# powerpartial.net
KiCad netlist of a schematic drawn in EAGLE
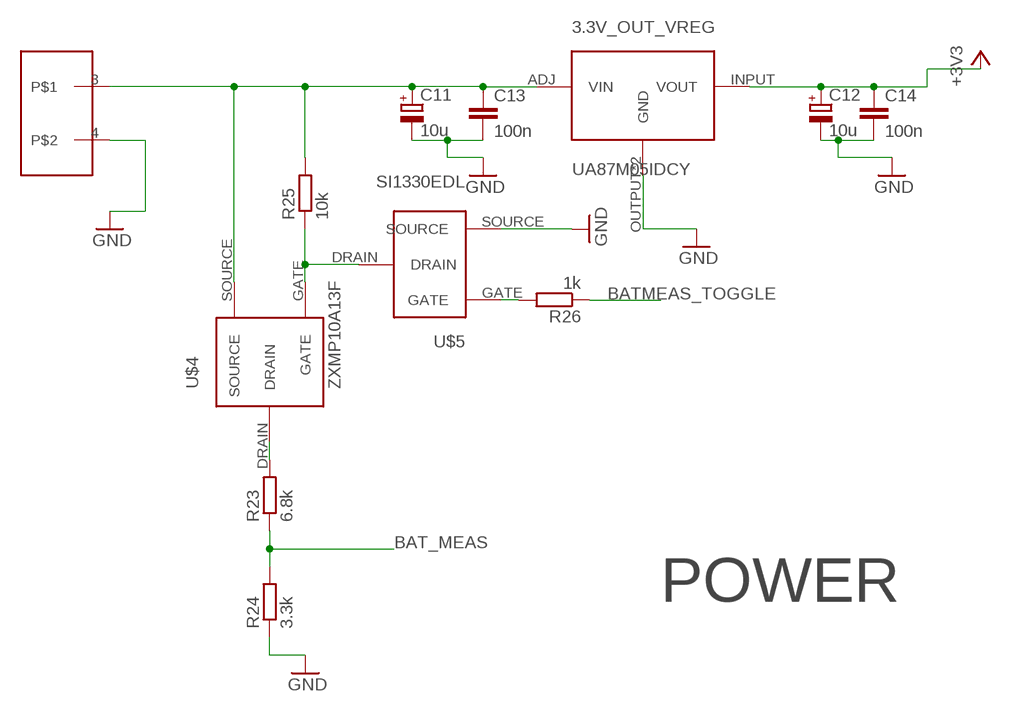
[diagram p0: schematic, sheet 1]

(export (version "E")
  (design (tool "Eeschema 10.0.6"))
  (components
    (comp (ref "3.3V_OUT_VREG")
      (value "UA87M05IDCY")
      (footprint "eagle-import:SOT223")
      (libsource (lib "eagle-import") (part "UA87M05IDCY"))
    )
    (comp (ref "C11")
      (value "10u")
      (footprint "eagle-import:153CLV-0505")
      (libsource (lib "eagle-import") (part "CPOL-EU153CLV-0505"))
    )
    (comp (ref "C12")
      (value "10u")
      (footprint "eagle-import:153CLV-0505")
      (libsource (lib "eagle-import") (part "CPOL-EU153CLV-0505"))
    )
    (comp (ref "C13")
      (value "100n")
      (footprint "eagle-import:C0805")
      (libsource (lib "eagle-import") (part "C-EUC0805"))
    )
    (comp (ref "C14")
      (value "100n")
      (footprint "eagle-import:C0805")
      (libsource (lib "eagle-import") (part "C-EUC0805"))
    )
    (comp (ref "R23")
      (value "6.8k")
      (footprint "eagle-import:R0805")
      (libsource (lib "eagle-import") (part "R-EU_R0805"))
    )
    (comp (ref "R24")
      (value "3.3k")
      (footprint "eagle-import:R0805")
      (libsource (lib "eagle-import") (part "R-EU_R0805"))
    )
    (comp (ref "R25")
      (value "10k")
      (footprint "eagle-import:R0805")
      (libsource (lib "eagle-import") (part "R-EU_R0805"))
    )
    (comp (ref "R26")
      (value "1k")
      (footprint "eagle-import:R0805")
      (libsource (lib "eagle-import") (part "R-EU_R0805"))
    )
    (comp (ref "SKRUVPLINT_2P5")
      (value "SKRUVPLINT_2P")
      (footprint "eagle-import:SKRUVPLINT_2P")
      (libsource (lib "eagle-import") (part "SKRUVPLINT_2P"))
    )
    (comp (ref "U$4")
      (value "ZXMP10A13F")
      (footprint "eagle-import:P-CHANNEL")
      (libsource (lib "eagle-import") (part "ZXMP10A13F"))
    )
    (comp (ref "U$5")
      (value "SI1330EDL")
      (footprint "eagle-import:SOT-323")
      (libsource (lib "eagle-import") (part "SI1330EDL"))
    )
  )
  (nets
    (net (code "1") (name "+3V3") (class "Default")
      (node (ref "3.3V_OUT_VREG") (pin "INPUT") (pinfunction "VOUT_INPUT") (pintype "bidirectional"))
      (node (ref "C12") (pin "+") (pinfunction "+_+") (pintype "passive"))
      (node (ref "C14") (pin "1") (pinfunction "1_1") (pintype "passive"))
    )
    (net (code "2") (name "/BATMEAS_TOGGLE") (class "Default")
      (node (ref "R26") (pin "1") (pinfunction "1_1") (pintype "passive"))
    )
    (net (code "3") (name "/BAT_MEAS") (class "Default")
      (node (ref "R23") (pin "1") (pinfunction "1_1") (pintype "passive"))
      (node (ref "R24") (pin "2") (pinfunction "2_2") (pintype "passive"))
    )
    (net (code "4") (name "GND") (class "Default")
      (node (ref "3.3V_OUT_VREG") (pin "OUTPUT") (pinfunction "GND_OUTPUT") (pintype "bidirectional"))
      (node (ref "3.3V_OUT_VREG") (pin "VOUT") (pinfunction "GND_VOUT") (pintype "bidirectional"))
      (node (ref "C11") (pin "-") (pinfunction "-_-") (pintype "passive"))
      (node (ref "C12") (pin "-") (pinfunction "-_-") (pintype "passive"))
      (node (ref "C13") (pin "2") (pinfunction "2_2") (pintype "passive"))
      (node (ref "C14") (pin "2") (pinfunction "2_2") (pintype "passive"))
      (node (ref "R24") (pin "1") (pinfunction "1_1") (pintype "passive"))
      (node (ref "SKRUVPLINT_2P5") (pin "4") (pinfunction "P$2_4") (pintype "bidirectional"))
      (node (ref "U$5") (pin "SOURCE") (pinfunction "SOURCE_SOURCE") (pintype "bidirectional"))
    )
    (net (code "5") (name "Net-(3.3V_OUT_VREG-VIN)") (class "Default")
      (node (ref "3.3V_OUT_VREG") (pin "ADJ") (pinfunction "VIN_ADJ") (pintype "bidirectional"))
      (node (ref "C11") (pin "+") (pinfunction "+_+") (pintype "passive"))
      (node (ref "C13") (pin "1") (pinfunction "1_1") (pintype "passive"))
      (node (ref "R25") (pin "2") (pinfunction "2_2") (pintype "passive"))
      (node (ref "SKRUVPLINT_2P5") (pin "3") (pinfunction "P$1_3") (pintype "bidirectional"))
      (node (ref "U$4") (pin "SOURCE") (pinfunction "SOURCE_SOURCE") (pintype "bidirectional"))
    )
    (net (code "6") (name "Net-(R23-Pad2)") (class "Default")
      (node (ref "R23") (pin "2") (pinfunction "2_2") (pintype "passive"))
      (node (ref "U$4") (pin "DRAIN") (pinfunction "DRAIN_DRAIN") (pintype "bidirectional"))
    )
    (net (code "7") (name "Net-(R25-Pad1)") (class "Default")
      (node (ref "R25") (pin "1") (pinfunction "1_1") (pintype "passive"))
      (node (ref "U$4") (pin "GATE") (pinfunction "GATE_GATE") (pintype "bidirectional"))
      (node (ref "U$5") (pin "DRAIN") (pinfunction "DRAIN_DRAIN") (pintype "bidirectional"))
    )
    (net (code "8") (name "Net-(R26-Pad2)") (class "Default")
      (node (ref "R26") (pin "2") (pinfunction "2_2") (pintype "passive"))
      (node (ref "U$5") (pin "GATE") (pinfunction "GATE_GATE") (pintype "bidirectional"))
    )
  )
)
